# 15_LMS2_RF1_Misc.net
KiCad netlist of a schematic drawn in Altium Designer
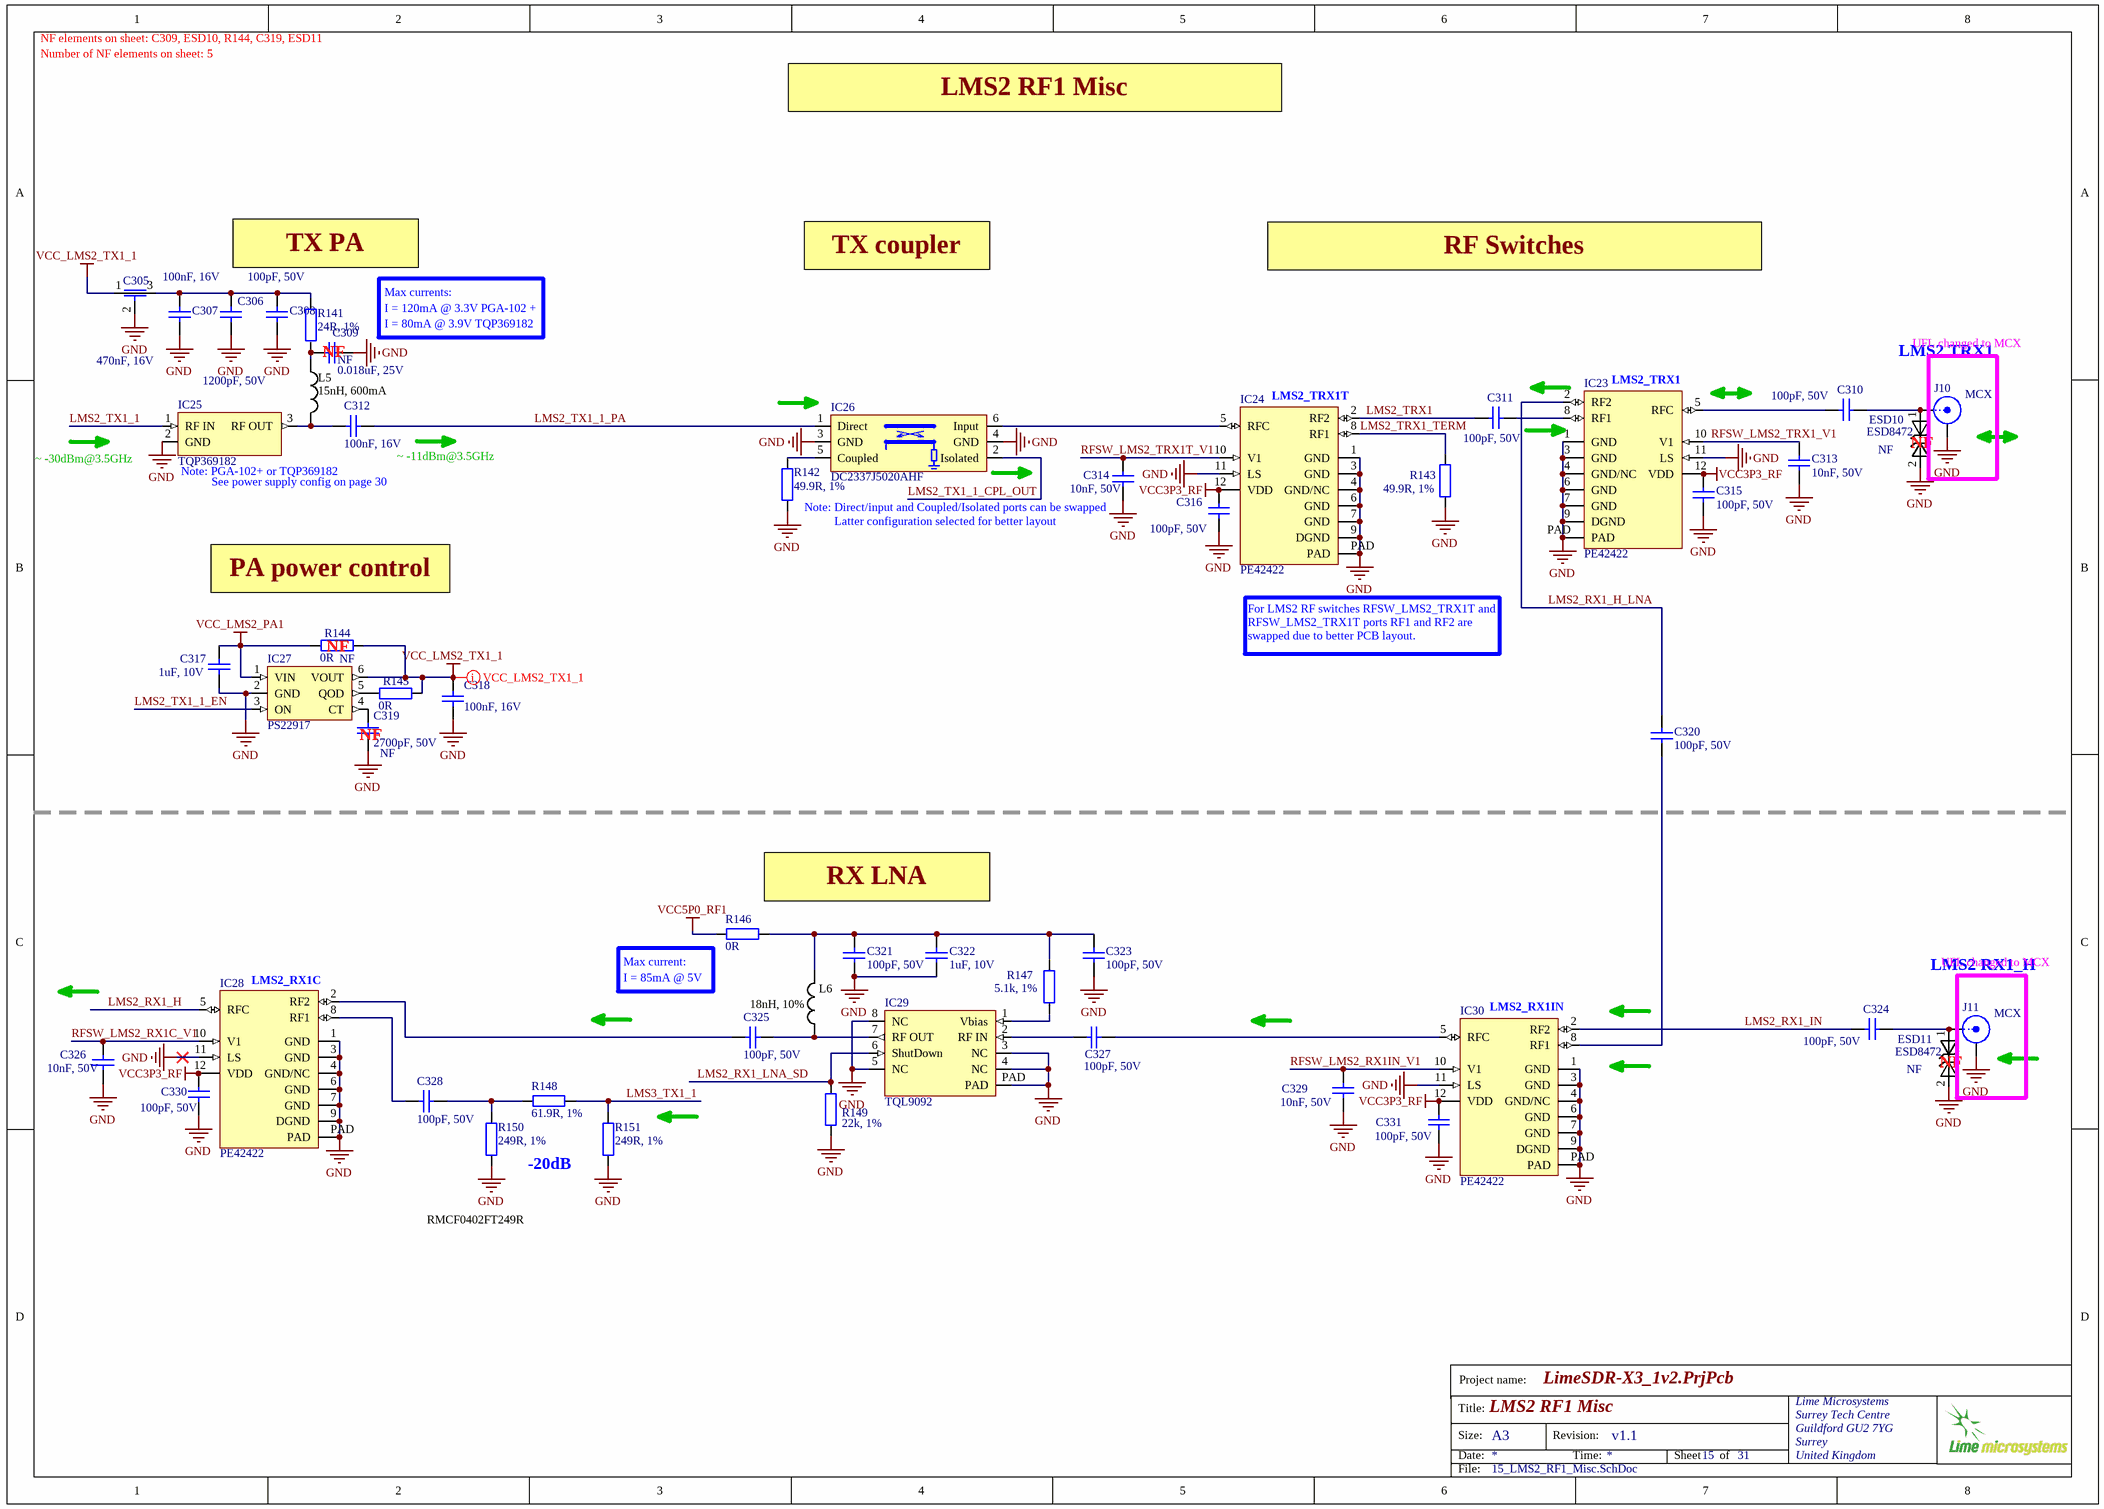
[diagram p0: 15_LMS2_RF1_Misc.SchDoc]

(export (version "E")
  (design (tool "Eeschema 10.0.6"))
  (components
    (comp (ref "C305")
      (value "470nF, 16V")
      (footprint "CAP0805_FEEDTHROUGH")
      (fields
        (field (name "MANUFACTURER") "Murata")
        (field (name "TOLERANCE") "20%")
        (field (name "VOLTAGE") "16V")
      )
      (libsource (lib "LimeMicroAltiumLib_schLib_r01") (part "Cap_feed_through"))
    )
    (comp (ref "C306")
      (value "1200pF, 50V")
      (footprint "CAP0402")
      (fields (field (name "MANUFACTURER") "Kemet") (field (name "TOLERANCE") "±5%"))
      (libsource (lib "") (part "Cap_0402_6"))
    )
    (comp (ref "C307")
      (value "100nF, 16V")
      (footprint "CAP0402")
      (fields (field (name "MANUFACTURER") "Murata Electronics") (field (name "TOLERANCE") "10 %"))
      (libsource (lib "") (part "Cap_0402_9"))
    )
    (comp (ref "C308")
      (value "100pF, 50V")
      (footprint "CAP0402")
      (fields (field (name "TOLERANCE") "±5%") (field (name "MANUFACTURER") "Yageo"))
      (libsource (lib "") (part "Cap_0402_9"))
    )
    (comp (ref "C309")
      (value "0.018uF, 25V")
      (footprint "CAP0402")
      (fields
        (field (name "ASSEMBLY INFO") "NF")
        (field (name "MANUFACTURER") "Yageo")
        (field (name "TOLERANCE") "10%")
      )
      (libsource (lib "") (part "Cap_0402_3"))
    )
    (comp (ref "C310")
      (value "100pF, 50V")
      (footprint "CAP0402")
      (fields (field (name "TOLERANCE") "±5%") (field (name "MANUFACTURER") "Yageo"))
      (libsource (lib "") (part "Cap_0402_4"))
    )
    (comp (ref "C311")
      (value "100pF, 50V")
      (footprint "CAP0402")
      (fields (field (name "TOLERANCE") "±5%") (field (name "MANUFACTURER") "Yageo"))
      (libsource (lib "") (part "Cap_0402_4"))
    )
    (comp (ref "C312")
      (value "100nF, 16V")
      (footprint "CAP0402")
      (fields (field (name "MANUFACTURER") "Murata Electronics") (field (name "TOLERANCE") "10 %"))
      (libsource (lib "LimeMicroAltiumLib_schLib") (part "Cap_0402"))
    )
    (comp (ref "C313")
      (value "10nF, 50V")
      (footprint "CAP0402")
      (fields
        (field (name "MANUFACTURER") "Murata Electronics North America")
        (field (name "TOLERANCE") "±10%")
      )
      (libsource (lib "") (part "Cap_0402_1"))
    )
    (comp (ref "C314")
      (value "10nF, 50V")
      (footprint "CAP0402")
      (fields
        (field (name "MANUFACTURER") "Murata Electronics North America")
        (field (name "TOLERANCE") "±10%")
      )
      (libsource (lib "") (part "Cap_0402_1"))
    )
    (comp (ref "C315")
      (value "100pF, 50V")
      (footprint "CAP0402")
      (fields (field (name "TOLERANCE") "±5%") (field (name "MANUFACTURER") "Yageo"))
      (libsource (lib "") (part "Cap_0402_10"))
    )
    (comp (ref "C316")
      (value "100pF, 50V")
      (footprint "CAP0402")
      (fields (field (name "TOLERANCE") "±5%") (field (name "MANUFACTURER") "Yageo"))
      (libsource (lib "") (part "Cap_0402_10"))
    )
    (comp (ref "C317")
      (value "1uF, 10V")
      (footprint "CAP0402")
      (fields (field (name "MANUFACTURER") "TDK"))
      (libsource (lib "") (part "Cap_0402_7"))
    )
    (comp (ref "C318")
      (value "100nF, 16V")
      (footprint "CAP0402")
      (fields (field (name "MANUFACTURER") "Murata Electronics") (field (name "TOLERANCE") "10 %"))
      (libsource (lib "") (part "Cap_0402_7"))
    )
    (comp (ref "C319")
      (value "2700pF, 50V")
      (footprint "CAP0402")
      (fields
        (field (name "ASSEMBLY INFO") "NF")
        (field (name "TOLERANCE") "±10%")
        (field (name "MANUFACTURER") "Murata Electronics North America")
      )
      (libsource (lib "") (part "Cap_0402_9"))
    )
    (comp (ref "C320")
      (value "100pF, 50V")
      (footprint "CAP0402")
      (fields (field (name "TOLERANCE") "±5%") (field (name "MANUFACTURER") "Yageo"))
      (libsource (lib "") (part "Cap_0402_4"))
    )
    (comp (ref "C321")
      (value "100pF, 50V")
      (footprint "CAP0402")
      (fields (field (name "TOLERANCE") "±5%") (field (name "MANUFACTURER") "Yageo"))
      (libsource (lib "") (part "Cap_0402_2"))
    )
    (comp (ref "C322")
      (value "1uF, 10V")
      (footprint "CAP0402")
      (fields (field (name "MANUFACTURER") "TDK"))
      (libsource (lib "") (part "Cap_0402_5"))
    )
    (comp (ref "C323")
      (value "100pF, 50V")
      (footprint "CAP0402")
      (fields (field (name "TOLERANCE") "±5%") (field (name "MANUFACTURER") "Yageo"))
      (libsource (lib "") (part "Cap_0402_2"))
    )
    (comp (ref "C324")
      (value "100pF, 50V")
      (footprint "CAP0402")
      (fields (field (name "TOLERANCE") "±5%") (field (name "MANUFACTURER") "Yageo"))
      (libsource (lib "") (part "Cap_0402_4"))
    )
    (comp (ref "C325")
      (value "100pF, 50V")
      (footprint "CAP0402")
      (fields (field (name "TOLERANCE") "±5%") (field (name "MANUFACTURER") "Yageo"))
      (libsource (lib "") (part "Cap_0402_7"))
    )
    (comp (ref "C326")
      (value "10nF, 50V")
      (footprint "CAP0402")
      (fields
        (field (name "MANUFACTURER") "Murata Electronics North America")
        (field (name "TOLERANCE") "±10%")
      )
      (libsource (lib "") (part "Cap_0402_11"))
    )
    (comp (ref "C327")
      (value "100pF, 50V")
      (footprint "CAP0402")
      (fields (field (name "TOLERANCE") "±5%") (field (name "MANUFACTURER") "Yageo"))
      (libsource (lib "") (part "Cap_0402_8"))
    )
    (comp (ref "C328")
      (value "100pF, 50V")
      (footprint "CAP0402")
      (fields (field (name "TOLERANCE") "±5%") (field (name "MANUFACTURER") "Yageo"))
      (libsource (lib "") (part "Cap_0402_4"))
    )
    (comp (ref "C329")
      (value "10nF, 50V")
      (footprint "CAP0402")
      (fields
        (field (name "MANUFACTURER") "Murata Electronics North America")
        (field (name "TOLERANCE") "±10%")
      )
      (libsource (lib "") (part "Cap_0402_3"))
    )
    (comp (ref "C330")
      (value "100pF, 50V")
      (footprint "CAP0402")
      (fields (field (name "TOLERANCE") "±5%") (field (name "MANUFACTURER") "Yageo"))
      (libsource (lib "") (part "Cap_0402_12"))
    )
    (comp (ref "C331")
      (value "100pF, 50V")
      (footprint "CAP0402")
      (fields (field (name "TOLERANCE") "±5%") (field (name "MANUFACTURER") "Yageo"))
      (libsource (lib "LimeMicroAltiumLib_schLib") (part "Cap_0402"))
    )
    (comp (ref "ESD10")
      (value "ESD8472")
      (footprint "ESD8472_X3DFN2")
      (fields (field (name "MANUFACTURER") "ON Semiconductor") (field (name "ASSEMBLY INFO") "NF"))
      (libsource (lib "LimeMicroAltiumLib_schLib") (part "ESD8472"))
    )
    (comp (ref "ESD11")
      (value "ESD8472")
      (footprint "ESD8472_X3DFN2")
      (fields (field (name "MANUFACTURER") "ON Semiconductor") (field (name "ASSEMBLY INFO") "NF"))
      (libsource (lib "") (part "ESD8472_1"))
    )
    (comp (ref "IC23")
      (value "PE42422")
      (footprint "PE42422_QFN12")
      (fields (field (name "MANUFACTURER") "Peregrine Semiconductor"))
      (libsource (lib "LimeMicroAltiumLib_schLib") (part "PE42422"))
    )
    (comp (ref "IC24")
      (value "PE42422")
      (footprint "PE42422_QFN12")
      (fields (field (name "MANUFACTURER") "Peregrine Semiconductor"))
      (libsource (lib "") (part "PE42422_3"))
    )
    (comp (ref "IC25")
      (value "TQP369182")
      (footprint "PGA-102+_SOT89")
      (fields (field (name "MANUFACTURER") "Qorvo"))
      (libsource (lib "LimeMicroAltiumLib_schLib_r01") (part "PGA-102+_PA"))
    )
    (comp (ref "IC26")
      (value "DC2337J5020AHF")
      (footprint "DC2337J5020AHF_ANAREN_COUPLER_0805")
      (fields (field (name "MANUFACTURER") "Anaren"))
      (libsource (lib "LimeMicroAltiumLib_schLib_r02") (part "DC2337J5020AHF_coupler"))
    )
    (comp (ref "IC27")
      (value "PS22917")
      (footprint "SOT23-6")
      (fields (field (name "MANUFACTURER") "Texas Instruments"))
      (libsource (lib "LimeMicroAltiumLib_schLib") (part "TPS22918"))
    )
    (comp (ref "IC28")
      (value "PE42422")
      (footprint "PE42422_QFN12")
      (fields (field (name "MANUFACTURER") "Peregrine Semiconductor"))
      (libsource (lib "") (part "PE42422_2"))
    )
    (comp (ref "IC29")
      (value "TQL9092")
      (footprint "TQL9092")
      (fields (field (name "MANUFACTURER") "Qorvo"))
      (libsource (lib "LimeMicroAltiumLib_schLib") (part "TQL9092"))
    )
    (comp (ref "IC30")
      (value "PE42422")
      (footprint "PE42422_QFN12")
      (fields (field (name "MANUFACTURER") "Peregrine Semiconductor"))
      (libsource (lib "") (part "PE42422_1"))
    )
    (comp (ref "J10")
      (value "MCX")
      (footprint "MCX_connector_vertical_SM")
      (description "Conn MCX RCP 0Hz to 6GHz 50Ohm Solder ST SMD Gold Over Nickel Stock")
      (fields (field (name "MANUFACTURER") "Bel Cinch"))
      (libsource (lib "LimeMicroAltiumLib_schLib") (part "RF_IF_connector"))
    )
    (comp (ref "J11")
      (value "MCX")
      (footprint "MCX_connector_vertical_SM")
      (description "Conn MCX RCP 0Hz to 6GHz 50Ohm Solder ST SMD Gold Over Nickel Stock")
      (fields (field (name "MANUFACTURER") "Bel Cinch"))
      (libsource (lib "LimeMicroAltiumLib_schLib") (part "RF_IF_connector"))
    )
    (comp (ref "L5")
      (value "15nH, 600mA")
      (footprint "RES0805")
      (fields (field (name "MANUFACTURER") "Bourns") (field (name "TOLERANCE") "5%"))
      (libsource (lib "LimeMicroAltiumLib_schLib") (part "Inductor_0603"))
    )
    (comp (ref "L6")
      (value "18nH, 10%")
      (footprint "RES0603")
      (fields (field (name "MANUFACTURER") "Pulse Electronics Network") (field (name "TOLERANCE") "±10%"))
      (libsource (lib "LimeMicroAltiumLib_schLib") (part "Inductor"))
    )
    (comp (ref "R141")
      (value "24R, 1%")
      (footprint "RES0402")
      (fields (field (name "MANUFACTURER") "Yageo") (field (name "TOLERANCE") "1%"))
      (libsource (lib "LimeFPGAboard_schLib") (part "Res_0402"))
    )
    (comp (ref "R142")
      (value "49.9R, 1%")
      (footprint "RES0402")
      (fields
        (field (name "TOLERANCE") "±1%")
        (field (name "MANUFACTURER") "Samsung Electro-Mechanics America, Inc.")
        (field (name "MANUFACTURER PART NUMBER") "RC1005F49R9CS")
      )
      (libsource (lib "") (part "Res_0402_1"))
    )
    (comp (ref "R143")
      (value "49.9R, 1%")
      (footprint "RES0402")
      (fields
        (field (name "TOLERANCE") "±1%")
        (field (name "MANUFACTURER") "Samsung Electro-Mechanics America, Inc.")
        (field (name "MANUFACTURER PART NUMBER") "RC1005F49R9CS")
      )
      (libsource (lib "") (part "Res_0402_1"))
    )
    (comp (ref "R144")
      (value "0R")
      (footprint "RES0402")
      (fields
        (field (name "ASSEMBLY INFO") "NF")
        (field (name "MANUFACTURER") "Yageo")
        (field (name "TOLERANCE") "Jumper")
      )
      (libsource (lib "LimeMicroAltiumLib_schLib") (part "Res_0402"))
    )
    (comp (ref "R145")
      (value "0R")
      (footprint "RES0402")
      (fields (field (name "MANUFACTURER") "Yageo") (field (name "TOLERANCE") "Jumper"))
      (libsource (lib "LimeMicroAltiumLib_schLib") (part "Res_0402"))
    )
    (comp (ref "R146")
      (value "0R")
      (footprint "RES0402")
      (fields (field (name "MANUFACTURER") "Yageo") (field (name "TOLERANCE") "Jumper"))
      (libsource (lib "") (part "Res_0402_1"))
    )
    (comp (ref "R147")
      (value "5.1k, 1%")
      (footprint "RES0603")
      (fields (field (name "MANUFACTURER") "Stackpole Electronics") (field (name "TOLERANCE") "1%"))
      (libsource (lib "LimeMicroAltiumLib_schLib") (part "Res_0603"))
    )
    (comp (ref "R148")
      (value "61.9R, 1%")
      (footprint "RES0402")
      (fields (field (name "MANUFACTURER") "Yageo") (field (name "TOLERANCE") "1%"))
      (libsource (lib "LimeMicroAltiumLib_schLib") (part "Res_0402"))
    )
    (comp (ref "R149")
      (value "22k, 1%")
      (footprint "RES0402")
      (fields (field (name "MANUFACTURER") "Yageo") (field (name "TOLERANCE") "±1%"))
      (libsource (lib "LimeMicroAltiumLib_schLib") (part "Res_0402"))
    )
    (comp (ref "R150")
      (value "249R, 1%")
      (footprint "RES0402")
      (fields (field (name "MANUFACTURER") "Stackpole Electronics Inc") (field (name "TOLERANCE") "±1%"))
      (libsource (lib "LimeMicroAltiumLib_schLib") (part "Res_0402"))
    )
    (comp (ref "R151")
      (value "249R, 1%")
      (footprint "RES0402")
      (fields (field (name "MANUFACTURER") "Stackpole Electronics Inc") (field (name "TOLERANCE") "±1%"))
      (libsource (lib "LimeMicroAltiumLib_schLib") (part "Res_0402"))
    )
  )
  (nets
    (net (code "1") (name "/LMS2_RX1_H") (class "Default")
      (node (ref "IC28") (pin "5") (pinfunction "RFC_5") (pintype "bidirectional"))
    )
    (net (code "2") (name "/LMS2_RX1_H_LNA") (class "Default")
      (node (ref "C320") (pin "2") (pinfunction "2_2") (pintype "passive"))
      (node (ref "IC23") (pin "2") (pinfunction "RF2_2") (pintype "bidirectional"))
    )
    (net (code "3") (name "/LMS2_RX1_IN") (class "Default")
      (node (ref "C324") (pin "1") (pinfunction "1_1") (pintype "passive"))
      (node (ref "IC30") (pin "2") (pinfunction "RF2_2") (pintype "bidirectional"))
    )
    (net (code "4") (name "/LMS2_RX1_LNA_SD") (class "Default")
      (node (ref "IC29") (pin "6") (pinfunction "ShutDown_6") (pintype "input"))
      (node (ref "R149") (pin "2") (pinfunction "2_2") (pintype "passive"))
    )
    (net (code "5") (name "/LMS2_TRX1") (class "Default")
      (node (ref "C311") (pin "1") (pinfunction "1_1") (pintype "passive"))
      (node (ref "IC24") (pin "2") (pinfunction "RF2_2") (pintype "bidirectional"))
    )
    (net (code "6") (name "/LMS2_TRX1_TERM") (class "Default")
      (node (ref "IC24") (pin "8") (pinfunction "RF1_8") (pintype "bidirectional"))
      (node (ref "R143") (pin "1") (pinfunction "1_1") (pintype "passive"))
    )
    (net (code "7") (name "/LMS2_TX1_1") (class "Default")
      (node (ref "IC25") (pin "1") (pinfunction "RF_IN_1") (pintype "input"))
    )
    (net (code "8") (name "/LMS2_TX1_1_CPL_OUT") (class "Default")
      (node (ref "IC26") (pin "2") (pinfunction "Isolated_2") (pintype "passive"))
    )
    (net (code "9") (name "/LMS2_TX1_1_EN") (class "Default")
      (node (ref "IC27") (pin "3") (pinfunction "ON_3") (pintype "input"))
    )
    (net (code "10") (name "/LMS2_TX1_1_PA") (class "Default")
      (node (ref "C312") (pin "1") (pinfunction "1_1") (pintype "passive"))
      (node (ref "IC26") (pin "1") (pinfunction "Direct_1") (pintype "passive"))
    )
    (net (code "11") (name "/LMS3_TX1_1") (class "Default")
      (node (ref "R148") (pin "2") (pinfunction "2_2") (pintype "passive"))
      (node (ref "R151") (pin "2") (pinfunction "2_2") (pintype "passive"))
    )
    (net (code "12") (name "/RFSW_LMS2_RX1C_V1") (class "Default")
      (node (ref "C326") (pin "1") (pinfunction "1_1") (pintype "passive"))
      (node (ref "IC28") (pin "10") (pinfunction "V1_10") (pintype "input"))
    )
    (net (code "13") (name "/RFSW_LMS2_RX1IN_V1") (class "Default")
      (node (ref "C329") (pin "1") (pinfunction "1_1") (pintype "passive"))
      (node (ref "IC30") (pin "10") (pinfunction "V1_10") (pintype "input"))
    )
    (net (code "14") (name "/RFSW_LMS2_TRX1T_V1") (class "Default")
      (node (ref "C314") (pin "1") (pinfunction "1_1") (pintype "passive"))
      (node (ref "IC24") (pin "10") (pinfunction "V1_10") (pintype "input"))
    )
    (net (code "15") (name "/RFSW_LMS2_TRX1_V1") (class "Default")
      (node (ref "C313") (pin "1") (pinfunction "1_1") (pintype "passive"))
      (node (ref "IC23") (pin "10") (pinfunction "V1_10") (pintype "input"))
    )
    (net (code "16") (name "GND") (class "Default")
      (node (ref "C305") (pin "2") (pinfunction "2_2") (pintype "passive"))
      (node (ref "C306") (pin "2") (pinfunction "2_2") (pintype "passive"))
      (node (ref "C307") (pin "1") (pinfunction "1_1") (pintype "passive"))
      (node (ref "C308") (pin "2") (pinfunction "2_2") (pintype "passive"))
      (node (ref "C309") (pin "2") (pinfunction "2_2") (pintype "passive"))
      (node (ref "C313") (pin "2") (pinfunction "2_2") (pintype "passive"))
      (node (ref "C314") (pin "2") (pinfunction "2_2") (pintype "passive"))
      (node (ref "C315") (pin "1") (pinfunction "1_1") (pintype "passive"))
      (node (ref "C316") (pin "1") (pinfunction "1_1") (pintype "passive"))
      (node (ref "C317") (pin "1") (pinfunction "1_1") (pintype "passive"))
      (node (ref "C318") (pin "1") (pinfunction "1_1") (pintype "passive"))
      (node (ref "C319") (pin "2") (pinfunction "2_2") (pintype "passive"))
      (node (ref "C321") (pin "2") (pinfunction "2_2") (pintype "passive"))
      (node (ref "C322") (pin "1") (pinfunction "1_1") (pintype "passive"))
      (node (ref "C323") (pin "2") (pinfunction "2_2") (pintype "passive"))
      (node (ref "C326") (pin "2") (pinfunction "2_2") (pintype "passive"))
      (node (ref "C329") (pin "2") (pinfunction "2_2") (pintype "passive"))
      (node (ref "C330") (pin "1") (pinfunction "1_1") (pintype "passive"))
      (node (ref "C331") (pin "1") (pinfunction "1_1") (pintype "passive"))
      (node (ref "ESD10") (pin "2") (pinfunction "2_2") (pintype "passive"))
      (node (ref "ESD11") (pin "2") (pinfunction "2_2") (pintype "passive"))
      (node (ref "IC23") (pin "1") (pinfunction "GND_1") (pintype "passive"))
      (node (ref "IC23") (pin "11") (pinfunction "LS_11") (pintype "input"))
      (node (ref "IC23") (pin "3") (pinfunction "GND_3") (pintype "passive"))
      (node (ref "IC23") (pin "4") (pinfunction "GND/NC_4") (pintype "passive"))
      (node (ref "IC23") (pin "6") (pinfunction "GND_6") (pintype "passive"))
      (node (ref "IC23") (pin "7") (pinfunction "GND_7") (pintype "passive"))
      (node (ref "IC23") (pin "9") (pinfunction "DGND_9") (pintype "passive"))
      (node (ref "IC23") (pin "PAD") (pinfunction "PAD_PAD") (pintype "passive"))
      (node (ref "IC24") (pin "1") (pinfunction "GND_1") (pintype "passive"))
      (node (ref "IC24") (pin "11") (pinfunction "LS_11") (pintype "input"))
      (node (ref "IC24") (pin "3") (pinfunction "GND_3") (pintype "passive"))
      (node (ref "IC24") (pin "4") (pinfunction "GND/NC_4") (pintype "passive"))
      (node (ref "IC24") (pin "6") (pinfunction "GND_6") (pintype "passive"))
      (node (ref "IC24") (pin "7") (pinfunction "GND_7") (pintype "passive"))
      (node (ref "IC24") (pin "9") (pinfunction "DGND_9") (pintype "passive"))
      (node (ref "IC24") (pin "PAD") (pinfunction "PAD_PAD") (pintype "passive"))
      (node (ref "IC25") (pin "2") (pinfunction "GND_2") (pintype "passive"))
      (node (ref "IC26") (pin "3") (pinfunction "GND_3") (pintype "passive"))
      (node (ref "IC26") (pin "4") (pinfunction "GND_4") (pintype "passive"))
      (node (ref "IC27") (pin "2") (pinfunction "GND_2") (pintype "passive"))
      (node (ref "IC28") (pin "1") (pinfunction "GND_1") (pintype "passive"))
      (node (ref "IC28") (pin "11") (pinfunction "LS_11") (pintype "input"))
      (node (ref "IC28") (pin "3") (pinfunction "GND_3") (pintype "passive"))
      (node (ref "IC28") (pin "4") (pinfunction "GND/NC_4") (pintype "passive"))
      (node (ref "IC28") (pin "6") (pinfunction "GND_6") (pintype "passive"))
      (node (ref "IC28") (pin "7") (pinfunction "GND_7") (pintype "passive"))
      (node (ref "IC28") (pin "9") (pinfunction "DGND_9") (pintype "passive"))
      (node (ref "IC28") (pin "PAD") (pinfunction "PAD_PAD") (pintype "passive"))
      (node (ref "IC29") (pin "3") (pinfunction "NC_3") (pintype "passive"))
      (node (ref "IC29") (pin "4") (pinfunction "NC_4") (pintype "passive"))
      (node (ref "IC29") (pin "5") (pinfunction "NC_5") (pintype "passive"))
      (node (ref "IC29") (pin "8") (pinfunction "NC_8") (pintype "passive"))
      (node (ref "IC29") (pin "PAD") (pinfunction "PAD_PAD") (pintype "passive"))
      (node (ref "IC30") (pin "1") (pinfunction "GND_1") (pintype "passive"))
      (node (ref "IC30") (pin "11") (pinfunction "LS_11") (pintype "input"))
      (node (ref "IC30") (pin "3") (pinfunction "GND_3") (pintype "passive"))
      (node (ref "IC30") (pin "4") (pinfunction "GND/NC_4") (pintype "passive"))
      (node (ref "IC30") (pin "6") (pinfunction "GND_6") (pintype "passive"))
      (node (ref "IC30") (pin "7") (pinfunction "GND_7") (pintype "passive"))
      (node (ref "IC30") (pin "9") (pinfunction "DGND_9") (pintype "passive"))
      (node (ref "IC30") (pin "PAD") (pinfunction "PAD_PAD") (pintype "passive"))
      (node (ref "J10") (pin "2") (pinfunction "Y_2") (pintype "passive"))
      (node (ref "J11") (pin "2") (pinfunction "Y_2") (pintype "passive"))
      (node (ref "R142") (pin "2") (pinfunction "2_2") (pintype "passive"))
      (node (ref "R143") (pin "2") (pinfunction "2_2") (pintype "passive"))
      (node (ref "R149") (pin "1") (pinfunction "1_1") (pintype "passive"))
      (node (ref "R150") (pin "1") (pinfunction "1_1") (pintype "passive"))
      (node (ref "R151") (pin "1") (pinfunction "1_1") (pintype "passive"))
    )
    (net (code "17") (name "Net-(C305-Pad3)") (class "Default")
      (node (ref "C305") (pin "3") (pinfunction "3_3") (pintype "passive"))
      (node (ref "C306") (pin "1") (pinfunction "1_1") (pintype "passive"))
      (node (ref "C307") (pin "2") (pinfunction "2_2") (pintype "passive"))
      (node (ref "C308") (pin "1") (pinfunction "1_1") (pintype "passive"))
      (node (ref "R141") (pin "1") (pinfunction "1_1") (pintype "passive"))
    )
    (net (code "18") (name "Net-(C309-Pad1)") (class "Default")
      (node (ref "C309") (pin "1") (pinfunction "1_1") (pintype "passive"))
      (node (ref "L5") (pin "1") (pinfunction "1_1") (pintype "passive"))
      (node (ref "R141") (pin "2") (pinfunction "2_2") (pintype "passive"))
    )
    (net (code "19") (name "Net-(C321-Pad1)") (class "Default")
      (node (ref "C321") (pin "1") (pinfunction "1_1") (pintype "passive"))
      (node (ref "C322") (pin "2") (pinfunction "2_2") (pintype "passive"))
      (node (ref "C323") (pin "1") (pinfunction "1_1") (pintype "passive"))
      (node (ref "L6") (pin "1") (pinfunction "1_1") (pintype "passive"))
      (node (ref "R146") (pin "2") (pinfunction "2_2") (pintype "passive"))
      (node (ref "R147") (pin "2") (pinfunction "2_2") (pintype "passive"))
    )
    (net (code "20") (name "Net-(C328-Pad1)") (class "Default")
      (node (ref "C328") (pin "1") (pinfunction "1_1") (pintype "passive"))
      (node (ref "R148") (pin "1") (pinfunction "1_1") (pintype "passive"))
      (node (ref "R150") (pin "2") (pinfunction "2_2") (pintype "passive"))
    )
    (net (code "21") (name "Net-(IC23-RF1)") (class "Default")
      (node (ref "C311") (pin "2") (pinfunction "2_2") (pintype "passive"))
      (node (ref "IC23") (pin "8") (pinfunction "RF1_8") (pintype "bidirectional"))
    )
    (net (code "22") (name "Net-(IC23-RFC)") (class "Default")
      (node (ref "C310") (pin "1") (pinfunction "1_1") (pintype "passive"))
      (node (ref "IC23") (pin "5") (pinfunction "RFC_5") (pintype "bidirectional"))
    )
    (net (code "23") (name "Net-(IC24-RFC)") (class "Default")
      (node (ref "IC24") (pin "5") (pinfunction "RFC_5") (pintype "bidirectional"))
      (node (ref "IC26") (pin "6") (pinfunction "Input_6") (pintype "passive"))
    )
    (net (code "24") (name "Net-(IC25-RF_OUT)") (class "Default")
      (node (ref "C312") (pin "2") (pinfunction "2_2") (pintype "passive"))
      (node (ref "IC25") (pin "3") (pinfunction "RF_OUT_3") (pintype "output"))
      (node (ref "L5") (pin "2") (pinfunction "2_2") (pintype "passive"))
    )
    (net (code "25") (name "Net-(IC26-Coupled)") (class "Default")
      (node (ref "IC26") (pin "5") (pinfunction "Coupled_5") (pintype "passive"))
      (node (ref "R142") (pin "1") (pinfunction "1_1") (pintype "passive"))
    )
    (net (code "26") (name "Net-(IC27-CT)") (class "Default")
      (node (ref "C319") (pin "1") (pinfunction "1_1") (pintype "passive"))
      (node (ref "IC27") (pin "4") (pinfunction "CT_4") (pintype "output"))
    )
    (net (code "27") (name "Net-(IC27-QOD)") (class "Default")
      (node (ref "IC27") (pin "5") (pinfunction "QOD_5") (pintype "output"))
      (node (ref "R145") (pin "2") (pinfunction "2_2") (pintype "passive"))
    )
    (net (code "28") (name "Net-(IC28-RF1)") (class "Default")
      (node (ref "C328") (pin "2") (pinfunction "2_2") (pintype "passive"))
      (node (ref "IC28") (pin "8") (pinfunction "RF1_8") (pintype "bidirectional"))
    )
    (net (code "29") (name "Net-(IC28-RF2)") (class "Default")
      (node (ref "C325") (pin "1") (pinfunction "1_1") (pintype "passive"))
      (node (ref "IC28") (pin "2") (pinfunction "RF2_2") (pintype "bidirectional"))
    )
    (net (code "30") (name "Net-(IC29-RF_IN)") (class "Default")
      (node (ref "C327") (pin "1") (pinfunction "1_1") (pintype "passive"))
      (node (ref "IC29") (pin "2") (pinfunction "RF_IN_2") (pintype "input"))
    )
    (net (code "31") (name "Net-(IC29-RF_OUT)") (class "Default")
      (node (ref "C325") (pin "2") (pinfunction "2_2") (pintype "passive"))
      (node (ref "IC29") (pin "7") (pinfunction "RF_OUT_7") (pintype "output"))
      (node (ref "L6") (pin "2") (pinfunction "2_2") (pintype "passive"))
    )
    (net (code "32") (name "Net-(IC29-Vbias)") (class "Default")
      (node (ref "IC29") (pin "1") (pinfunction "Vbias_1") (pintype "input"))
      (node (ref "R147") (pin "1") (pinfunction "1_1") (pintype "passive"))
    )
    (net (code "33") (name "Net-(IC30-RF1)") (class "Default")
      (node (ref "C320") (pin "1") (pinfunction "1_1") (pintype "passive"))
      (node (ref "IC30") (pin "8") (pinfunction "RF1_8") (pintype "bidirectional"))
    )
    (net (code "34") (name "Net-(IC30-RFC)") (class "Default")
      (node (ref "C327") (pin "2") (pinfunction "2_2") (pintype "passive"))
      (node (ref "IC30") (pin "5") (pinfunction "RFC_5") (pintype "bidirectional"))
    )
    (net (code "35") (name "Net-(J10-X)") (class "Default")
      (node (ref "C310") (pin "2") (pinfunction "2_2") (pintype "passive"))
      (node (ref "ESD10") (pin "1") (pinfunction "1_1") (pintype "passive"))
      (node (ref "J10") (pin "1") (pinfunction "X_1") (pintype "passive"))
    )
    (net (code "36") (name "Net-(J11-X)") (class "Default")
      (node (ref "C324") (pin "2") (pinfunction "2_2") (pintype "passive"))
      (node (ref "ESD11") (pin "1") (pinfunction "1_1") (pintype "passive"))
      (node (ref "J11") (pin "1") (pinfunction "X_1") (pintype "passive"))
    )
    (net (code "37") (name "VCC3P3_RF") (class "Default")
      (node (ref "C315") (pin "2") (pinfunction "2_2") (pintype "passive"))
      (node (ref "C316") (pin "2") (pinfunction "2_2") (pintype "passive"))
      (node (ref "C330") (pin "2") (pinfunction "2_2") (pintype "passive"))
      (node (ref "C331") (pin "2") (pinfunction "2_2") (pintype "passive"))
      (node (ref "IC23") (pin "12") (pinfunction "VDD_12") (pintype "power_in"))
      (node (ref "IC24") (pin "12") (pinfunction "VDD_12") (pintype "power_in"))
      (node (ref "IC28") (pin "12") (pinfunction "VDD_12") (pintype "power_in"))
      (node (ref "IC30") (pin "12") (pinfunction "VDD_12") (pintype "power_in"))
    )
    (net (code "38") (name "VCC5P0_RF1") (class "Default")
      (node (ref "R146") (pin "1") (pinfunction "1_1") (pintype "passive"))
    )
    (net (code "39") (name "VCC_LMS2_PA1") (class "Default")
      (node (ref "C317") (pin "2") (pinfunction "2_2") (pintype "passive"))
      (node (ref "IC27") (pin "1") (pinfunction "VIN_1") (pintype "input"))
      (node (ref "R144") (pin "2") (pinfunction "2_2") (pintype "passive"))
    )
    (net (code "40") (name "VCC_LMS2_TX1_1") (class "Default")
      (node (ref "C305") (pin "1") (pinfunction "1_1") (pintype "passive"))
      (node (ref "C318") (pin "2") (pinfunction "2_2") (pintype "passive"))
      (node (ref "IC27") (pin "6") (pinfunction "VOUT_6") (pintype "output"))
      (node (ref "R144") (pin "1") (pinfunction "1_1") (pintype "passive"))
      (node (ref "R145") (pin "1") (pinfunction "1_1") (pintype "passive"))
    )
  )
)
